# InkTime.net
KiCad netlist of a schematic drawn in EAGLE
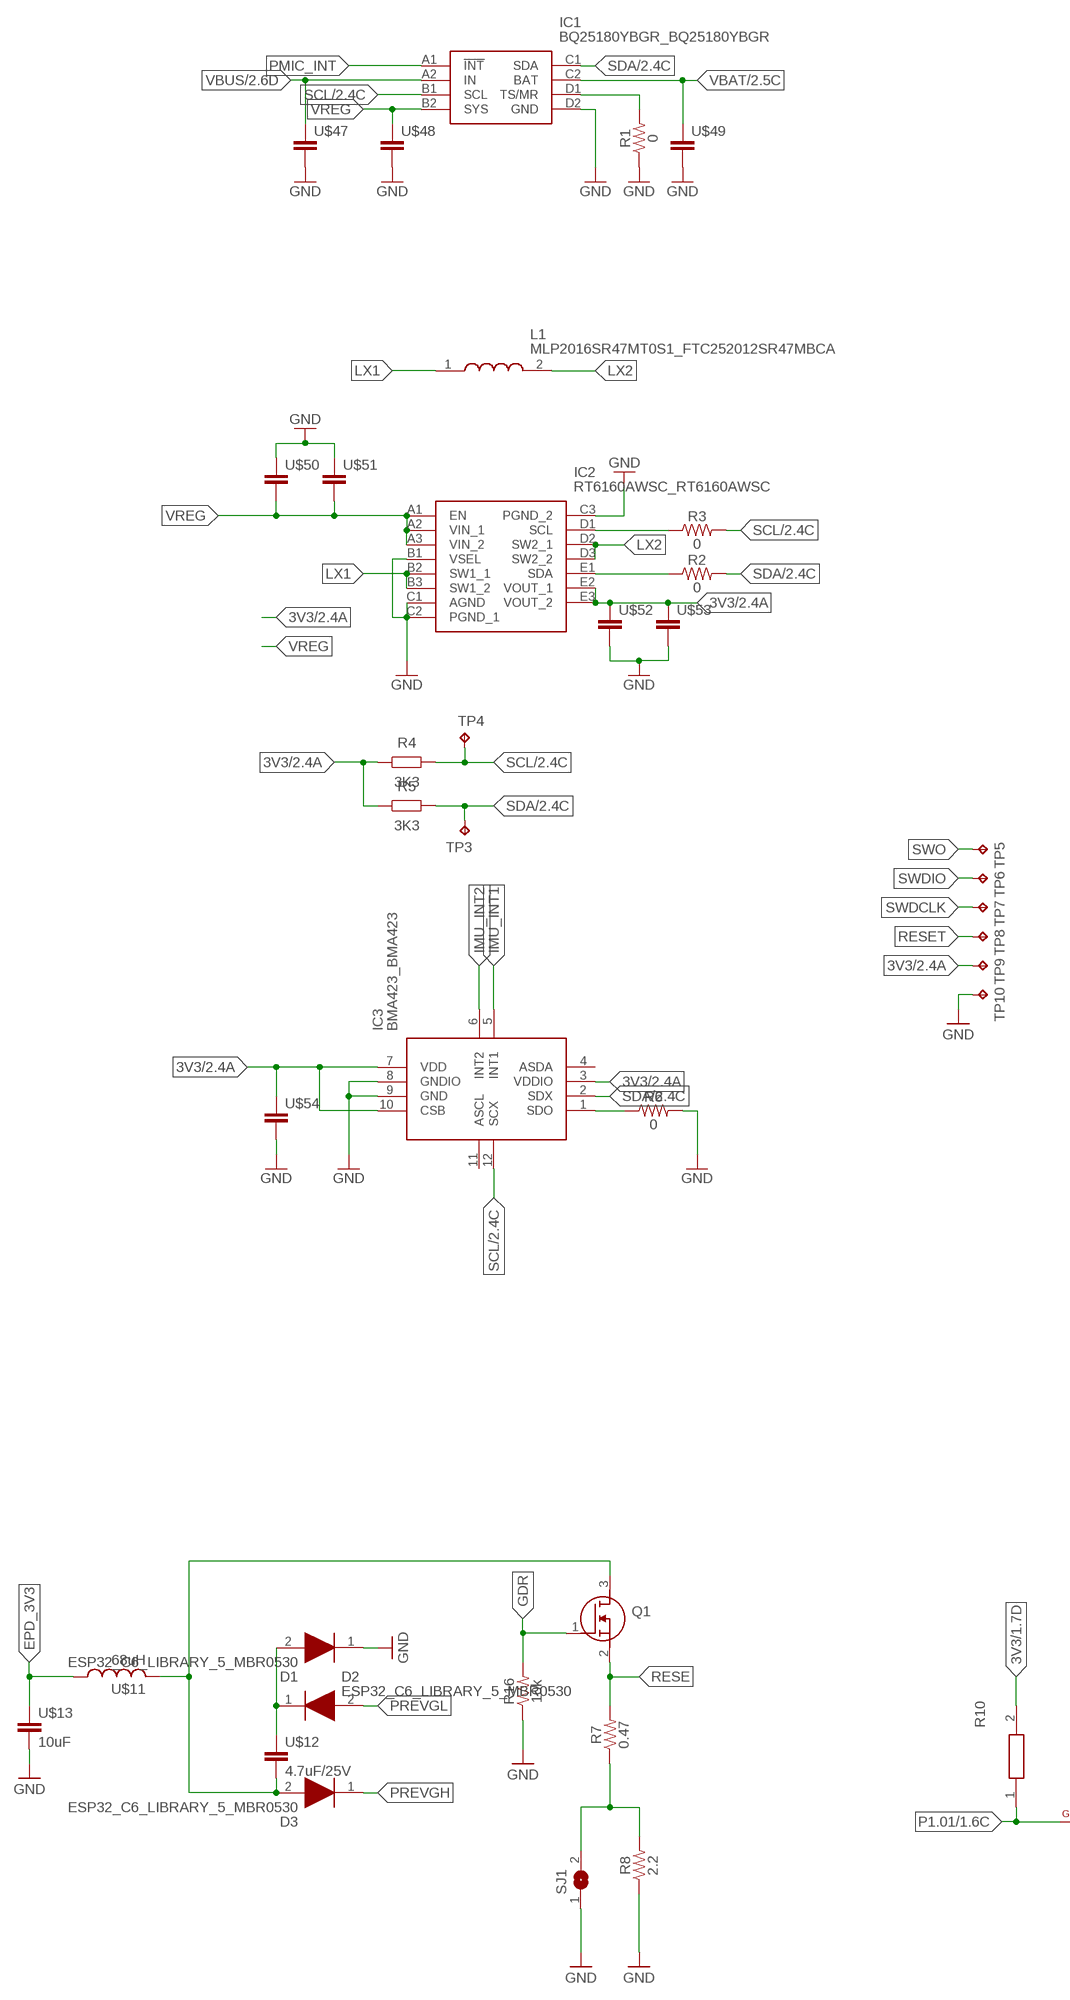
[diagram p0: schematic, sheet 1, part 1 of 3]
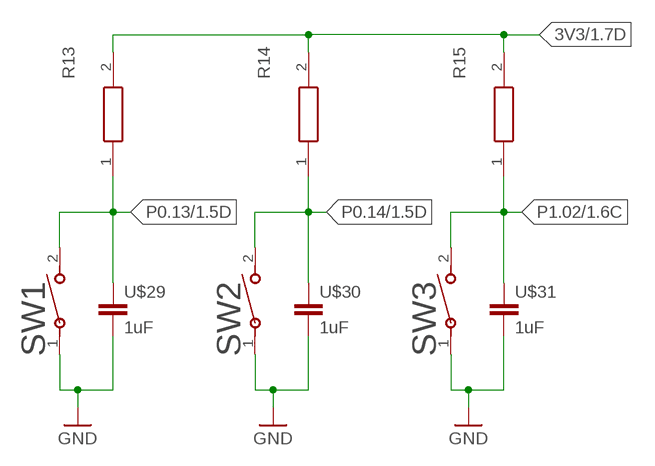
[diagram p1: schematic, sheet 1, part 2 of 3]
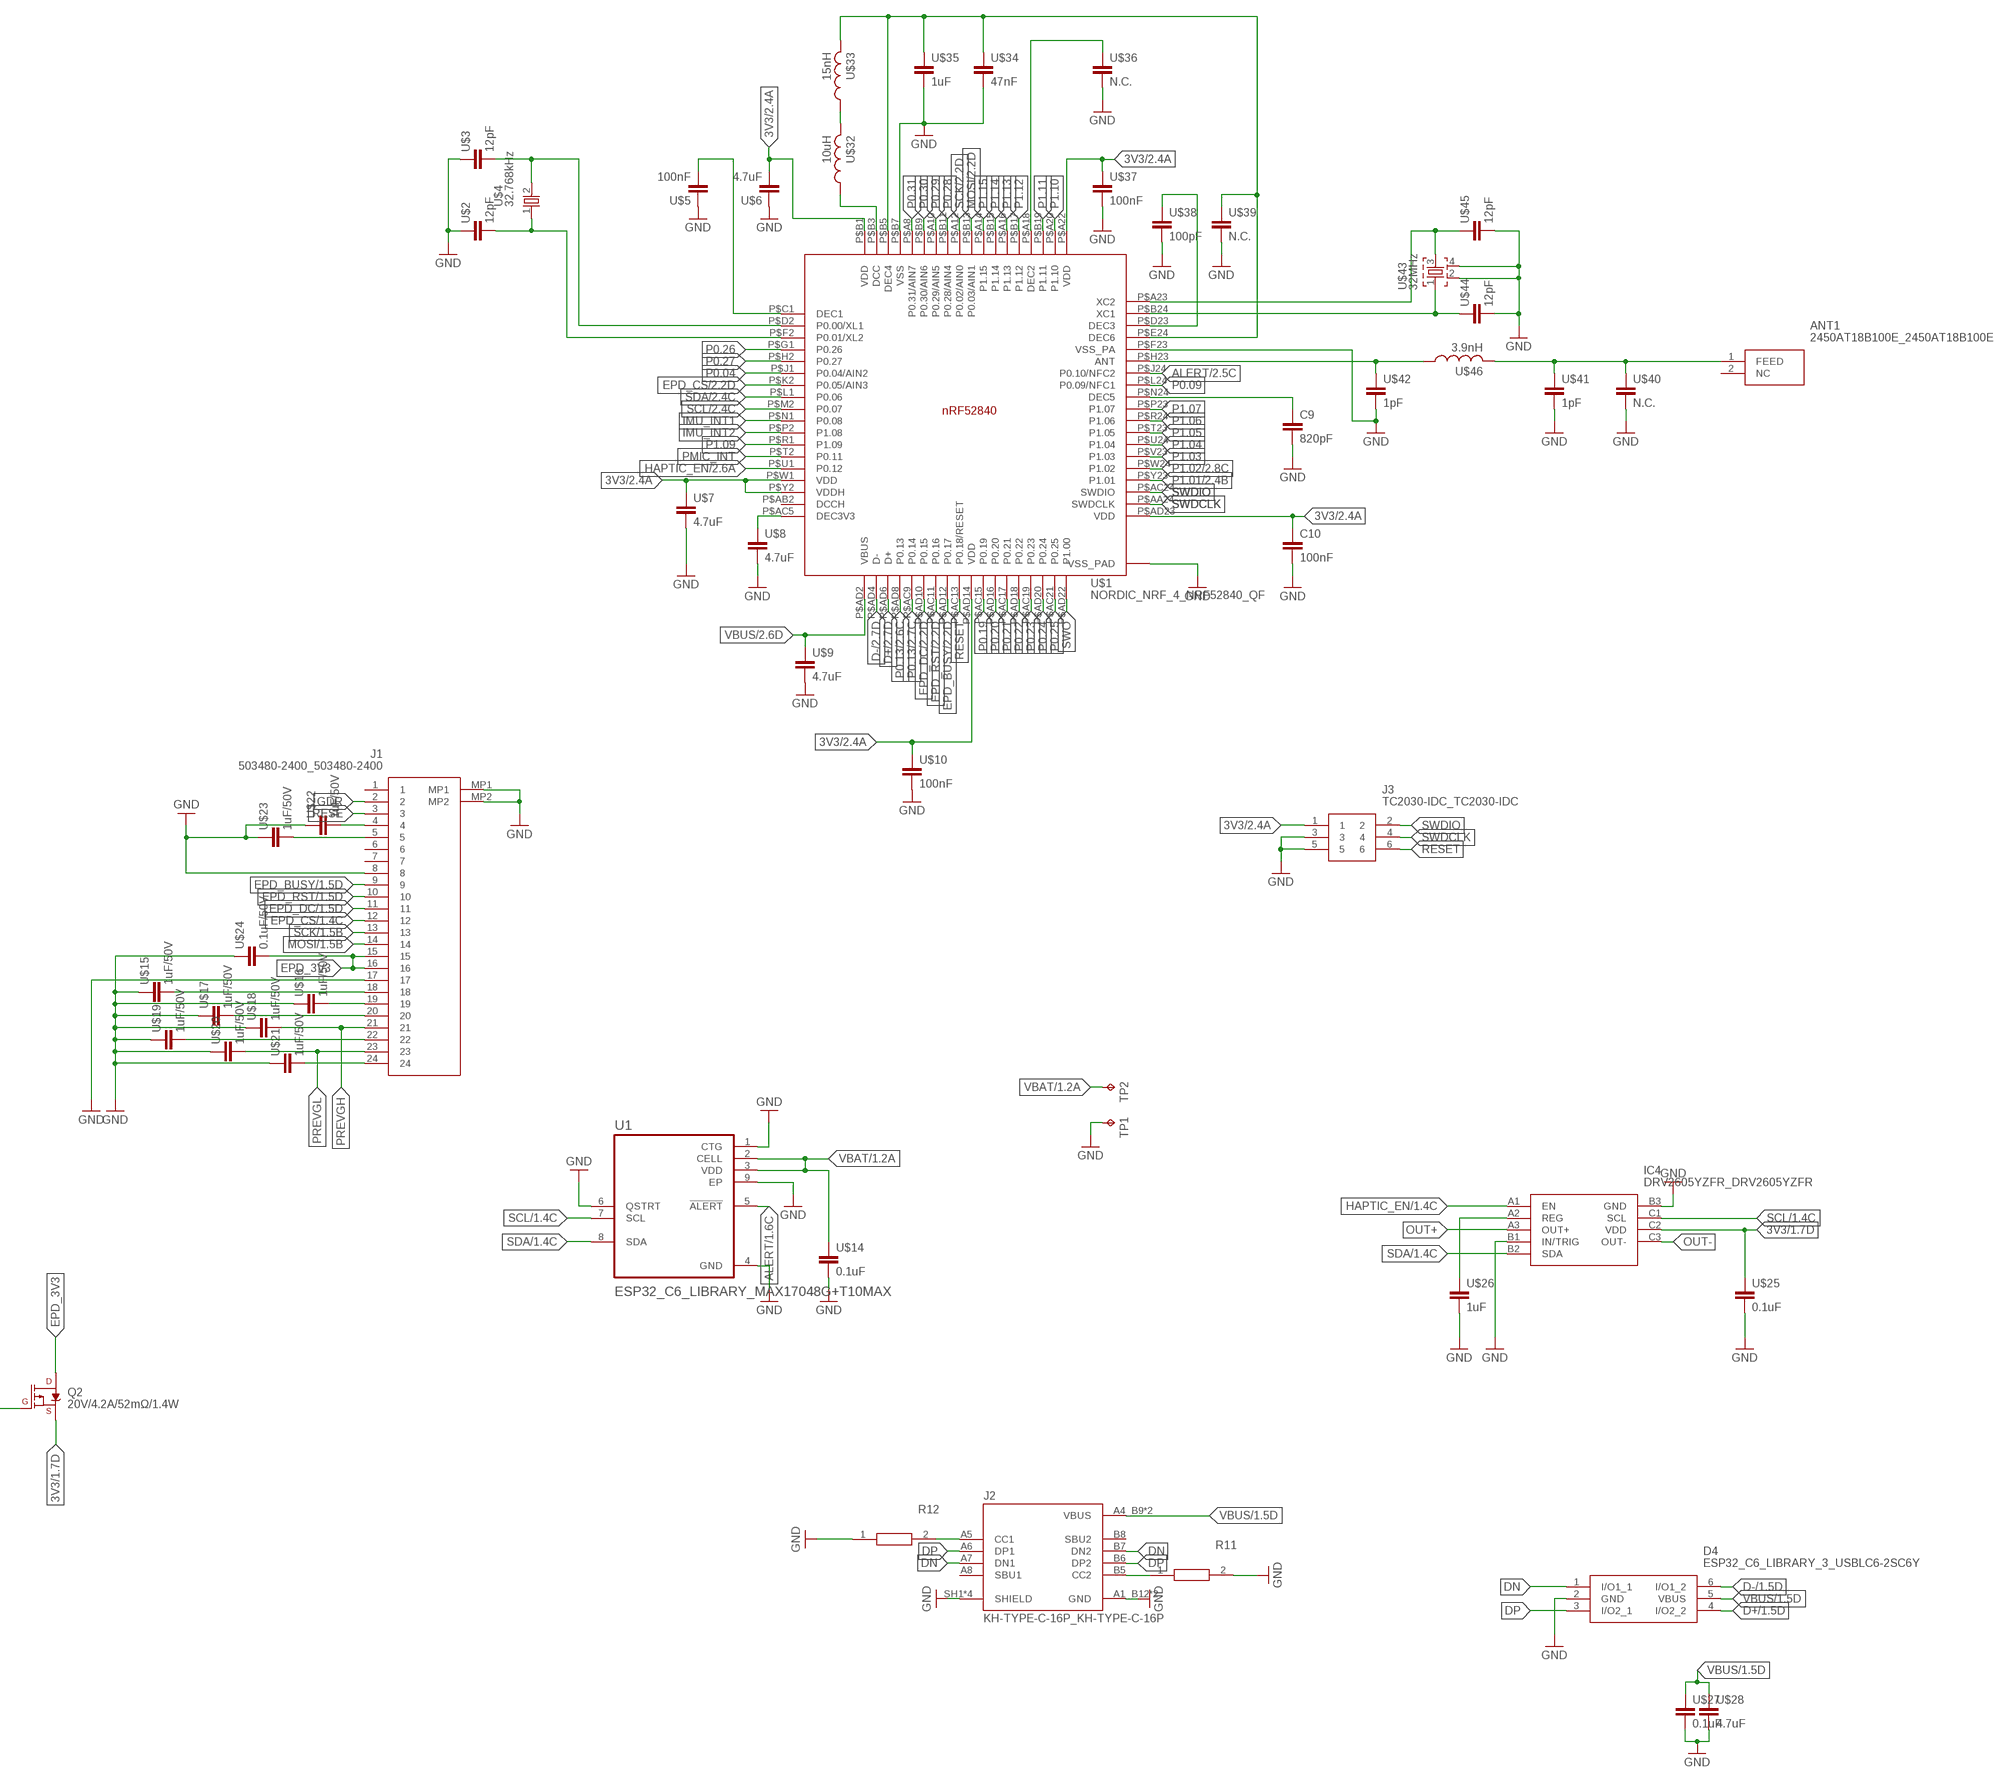
[diagram p2: schematic, sheet 1, part 3 of 3]

(export (version "E")
  (design (tool "Eeschema 10.0.6"))
  (components
    (comp (ref "ANT1")
      (value "2450AT18B100E_2450AT18B100E")
      (footprint "eagle-import:2450AT18B100E_ANTC3216X140N")
      (fields
        (field (name "ARROW_PART_NUMBER") "2450AT18B100E")
        (field (name "MOUSER_PART_NUMBER") "609-2450AT18B100E")
      )
      (libsource (lib "eagle-import") (part "2450AT18B100E_2450AT18B100E"))
    )
    (comp (ref "C9")
      (value "820pF")
      (footprint "eagle-import:PERFECT_0402_0402")
      (libsource (lib "eagle-import") (part "PERFECT_0402_CAP_0402"))
    )
    (comp (ref "C10")
      (value "100nF")
      (footprint "eagle-import:PERFECT_0402_0402")
      (libsource (lib "eagle-import") (part "PERFECT_0402_CAP_0402"))
    )
    (comp (ref "D1")
      (value "ESP32_C6_LIBRARY_5_MBR0530")
      (footprint "eagle-import:ESP32_C6_LIBRARY_5_SOD3716X135N")
      (fields (field (name "MF") "ON Semiconductor") (field (name "MP") "MBR0530"))
      (libsource (lib "eagle-import") (part "ESP32_C6_LIBRARY_5_MBR0530"))
    )
    (comp (ref "D2")
      (value "ESP32_C6_LIBRARY_5_MBR0530")
      (footprint "eagle-import:ESP32_C6_LIBRARY_5_SOD3716X135N")
      (fields (field (name "MF") "ON Semiconductor") (field (name "MP") "MBR0530"))
      (libsource (lib "eagle-import") (part "ESP32_C6_LIBRARY_5_MBR0530"))
    )
    (comp (ref "D3")
      (value "ESP32_C6_LIBRARY_5_MBR0530")
      (footprint "eagle-import:ESP32_C6_LIBRARY_5_SOD3716X135N")
      (fields (field (name "MF") "ON Semiconductor") (field (name "MP") "MBR0530"))
      (libsource (lib "eagle-import") (part "ESP32_C6_LIBRARY_5_MBR0530"))
    )
    (comp (ref "D4")
      (value "ESP32_C6_LIBRARY_3_USBLC6-2SC6Y")
      (footprint "eagle-import:ESP32_C6_LIBRARY_3_SOT95P280X145-6N")
      (fields (field (name "MF") "STMicroelectronics") (field (name "MP") "USBLC6-2SC6Y"))
      (libsource (lib "eagle-import") (part "ESP32_C6_LIBRARY_3_USBLC6-2SC6Y"))
    )
    (comp (ref "IC1")
      (value "BQ25180YBGR_BQ25180YBGR")
      (footprint "eagle-import:BQ25180YBGR_BGA8C40P2X4_100X155X50")
      (fields
        (field (name "ARROW_PART_NUMBER") "BQ25180YBGR")
        (field (name "MOUSER_PART_NUMBER") "595-BQ25180YBGR")
      )
      (libsource (lib "eagle-import") (part "BQ25180YBGR_BQ25180YBGR"))
    )
    (comp (ref "IC2")
      (value "RT6160AWSC_RT6160AWSC")
      (footprint "eagle-import:RT6160AWSC_BGA15C40P3X5_140X230X60")
      (fields
        (field (name "MANUFACTURER_PART_NUMBER") "RT6160AWSC")
        (field (name "MOUSER_PART_NUMBER") "835-RT6160AWSC")
      )
      (libsource (lib "eagle-import") (part "RT6160AWSC_RT6160AWSC"))
    )
    (comp (ref "IC3")
      (value "BMA423_BMA423")
      (footprint "eagle-import:BMA423_BMA423")
      (fields (field (name "ARROW_PART_NUMBER") "BMA423") (field (name "MOUSER_PART_NUMBER") "262-BMA423"))
      (libsource (lib "eagle-import") (part "BMA423_BMA423"))
    )
    (comp (ref "IC4")
      (value "DRV2605YZFR_DRV2605YZFR")
      (footprint "eagle-import:DRV2605YZFR_BGA9C50P3X3_144X144X62")
      (fields (field (name "ARROW_PART_NUMBER") "DRV2605YZFR"))
      (libsource (lib "eagle-import") (part "DRV2605YZFR_DRV2605YZFR"))
    )
    (comp (ref "J1")
      (value "503480-2400_503480-2400")
      (footprint "eagle-import:503480-2400_5034802400")
      (fields
        (field (name "MANUFACTURER_PART_NUMBER") "503480-2400")
        (field (name "MOUSER_PART_NUMBER") "538-503480-2400")
      )
      (libsource (lib "eagle-import") (part "503480-2400_503480-2400"))
    )
    (comp (ref "J2")
      (value "KH-TYPE-C-16P_KH-TYPE-C-16P")
      (footprint "eagle-import:KH-TYPE-C-16P_KINGHELM_KH-TYPE-C-16P")
      (fields (field (name "MF") "kinghelm") (field (name "MP") "KH-TYPE-C-16P"))
      (libsource (lib "eagle-import") (part "KH-TYPE-C-16P_KH-TYPE-C-16P"))
    )
    (comp (ref "J3")
      (value "TC2030-IDC_TC2030-IDC")
      (footprint "eagle-import:TC2030-IDC_TC2030IDC")
      (fields (field (name "MANUFACTURER_PART_NUMBER") "TC2030-IDC"))
      (libsource (lib "eagle-import") (part "TC2030-IDC_TC2030-IDC"))
    )
    (comp (ref "L1")
      (value "MLP2016SR47MT0S1_FTC252012SR47MBCA")
      (footprint "eagle-import:MLP2016SR47MT0S1_INDC2016X100N")
      (fields (field (name "MANUFACTURER_PART_NUMBER") "FTC252012SR47MBCA"))
      (libsource (lib "eagle-import") (part "MLP2016SR47MT0S1_FTC252012SR47MBCA"))
    )
    (comp (ref "Q1")
      (value "ESP32_C6_LIBRARY_6_SI1308EDL-T1-GE3")
      (footprint "eagle-import:ESP32_C6_LIBRARY_6_SOT65P210X110-3N")
      (fields (field (name "MF") "Vishay Siliconix") (field (name "MP") "SI1308EDL-T1-GE3"))
      (libsource (lib "eagle-import") (part "ESP32_C6_LIBRARY_6_SI1308EDL-T1-GE3"))
    )
    (comp (ref "Q2")
      (value "20V/4.2A/52mΩ/1.4W")
      (footprint "eagle-import:ESP32_C6_LIBRARY_4_ESP32_C6_LIBRARY_4_ESP32_C6_LIBRARY_4_ESP32_C6_LIBRARY_4_ESP32_WROVER_SPARKFUN-DISCRETESEMI_SOT23-3")
      (libsource (lib "eagle-import") (part "ESP32_C6_LIBRARY_4_ESP32_WROVER_SPARKFUN-DISCRETESEMI_MOSFET_PCH-DMG2305UX-7"))
    )
    (comp (ref "R1")
      (value "0")
      (footprint "eagle-import:0603")
      (libsource (lib "eagle-import") (part "0OHM-0603-1/10W"))
    )
    (comp (ref "R2")
      (value "0")
      (footprint "eagle-import:0603")
      (libsource (lib "eagle-import") (part "0OHM-0603-1/10W"))
    )
    (comp (ref "R3")
      (value "0")
      (footprint "eagle-import:0603")
      (libsource (lib "eagle-import") (part "0OHM-0603-1/10W"))
    )
    (comp (ref "R4")
      (value "3K3")
      (footprint "eagle-import:RESC1005X40")
      (libsource (lib "eagle-import") (part "RCHIP-0402(1005-METRIC)_"))
    )
    (comp (ref "R5")
      (value "3K3")
      (footprint "eagle-import:RESC1005X40")
      (libsource (lib "eagle-import") (part "RCHIP-0402(1005-METRIC)_"))
    )
    (comp (ref "R6")
      (value "0")
      (footprint "eagle-import:0603")
      (libsource (lib "eagle-import") (part "0OHM-0603-1/10W"))
    )
    (comp (ref "R7")
      (value "0.47")
      (footprint "eagle-import:0603")
      (libsource (lib "eagle-import") (part "0OHM-0603-1/10W"))
    )
    (comp (ref "R8")
      (value "2.2")
      (footprint "eagle-import:0603")
      (libsource (lib "eagle-import") (part "0OHM-0603-1/10W"))
    )
    (comp (ref "R10")
      (value "CPF0201D7K68C1_CPF0201D7K68C1")
      (footprint "eagle-import:CPF0201D7K68C1_0201")
      (libsource (lib "eagle-import") (part "CPF0201D7K68C1_CPF0201D7K68C1"))
    )
    (comp (ref "R11")
      (value "CPF0201D7K68C1_CPF0201D7K68C1")
      (footprint "eagle-import:CPF0201D7K68C1_0201")
      (libsource (lib "eagle-import") (part "CPF0201D7K68C1_CPF0201D7K68C1"))
    )
    (comp (ref "R12")
      (value "5k1")
      (footprint "eagle-import:CPF0201D7K68C1_0201")
      (libsource (lib "eagle-import") (part "CPF0201D7K68C1_CPF0201D7K68C1"))
    )
    (comp (ref "R13")
      (value "CPF0201D7K68C1_CPF0201D7K68C1")
      (footprint "eagle-import:CPF0201D7K68C1_0201")
      (libsource (lib "eagle-import") (part "CPF0201D7K68C1_CPF0201D7K68C1"))
    )
    (comp (ref "R14")
      (value "CPF0201D7K68C1_CPF0201D7K68C1")
      (footprint "eagle-import:CPF0201D7K68C1_0201")
      (libsource (lib "eagle-import") (part "CPF0201D7K68C1_CPF0201D7K68C1"))
    )
    (comp (ref "R15")
      (value "CPF0201D7K68C1_CPF0201D7K68C1")
      (footprint "eagle-import:CPF0201D7K68C1_0201")
      (libsource (lib "eagle-import") (part "CPF0201D7K68C1_CPF0201D7K68C1"))
    )
    (comp (ref "R16")
      (value "10k")
      (footprint "eagle-import:0603")
      (libsource (lib "eagle-import") (part "0OHM-0603-1/10W"))
    )
    (comp (ref "SJ1")
      (value "ESP32_C6_LIBRARY_7_JUMPER_SJ")
      (footprint "eagle-import:ESP32_C6_LIBRARY_7_JUMPER_SJ")
      (libsource (lib "eagle-import") (part "ESP32_C6_LIBRARY_7_JUMPER_SJ"))
    )
    (comp (ref "SW1")
      (value "2025-10-22_07-23-44_LIBRARY_EVP-AKE31AEVP-AKE31A")
      (footprint "eagle-import:2025-10-22_07-23-44_LIBRARY_SW_EVP-AKE31A_PAN")
      (libsource (lib "eagle-import") (part "2025-10-22_07-23-44_LIBRARY_EVP-AKE31AEVP-AKE31A"))
    )
    (comp (ref "SW2")
      (value "2025-10-22_07-23-44_LIBRARY_EVP-AKE31AEVP-AKE31A")
      (footprint "eagle-import:2025-10-22_07-23-44_LIBRARY_SW_EVP-AKE31A_PAN")
      (libsource (lib "eagle-import") (part "2025-10-22_07-23-44_LIBRARY_EVP-AKE31AEVP-AKE31A"))
    )
    (comp (ref "SW3")
      (value "2025-10-22_07-23-44_LIBRARY_EVP-AKE31AEVP-AKE31A")
      (footprint "eagle-import:2025-10-22_07-23-44_LIBRARY_SW_EVP-AKE31A_PAN")
      (libsource (lib "eagle-import") (part "2025-10-22_07-23-44_LIBRARY_EVP-AKE31AEVP-AKE31A"))
    )
    (comp (ref "TP1")
      (value "HECTOR_WATCH_1_TPTP20R")
      (footprint "eagle-import:HECTOR_WATCH_1_TP20R")
      (libsource (lib "eagle-import") (part "HECTOR_WATCH_1_TPTP20R"))
    )
    (comp (ref "TP2")
      (value "HECTOR_WATCH_1_TPTP20R")
      (footprint "eagle-import:HECTOR_WATCH_1_TP20R")
      (libsource (lib "eagle-import") (part "HECTOR_WATCH_1_TPTP20R"))
    )
    (comp (ref "TP3")
      (value "HECTOR_WATCH_1_TPTP20R")
      (footprint "eagle-import:HECTOR_WATCH_1_TP20R")
      (libsource (lib "eagle-import") (part "HECTOR_WATCH_1_TPTP20R"))
    )
    (comp (ref "TP4")
      (value "HECTOR_WATCH_1_TPTP20R")
      (footprint "eagle-import:HECTOR_WATCH_1_TP20R")
      (libsource (lib "eagle-import") (part "HECTOR_WATCH_1_TPTP20R"))
    )
    (comp (ref "TP5")
      (value "HECTOR_WATCH_1_TPTP20R")
      (footprint "eagle-import:HECTOR_WATCH_1_TP20R")
      (libsource (lib "eagle-import") (part "HECTOR_WATCH_1_TPTP20R"))
    )
    (comp (ref "TP6")
      (value "HECTOR_WATCH_1_TPTP20R")
      (footprint "eagle-import:HECTOR_WATCH_1_TP20R")
      (libsource (lib "eagle-import") (part "HECTOR_WATCH_1_TPTP20R"))
    )
    (comp (ref "TP7")
      (value "HECTOR_WATCH_1_TPTP20R")
      (footprint "eagle-import:HECTOR_WATCH_1_TP20R")
      (libsource (lib "eagle-import") (part "HECTOR_WATCH_1_TPTP20R"))
    )
    (comp (ref "TP8")
      (value "HECTOR_WATCH_1_TPTP20R")
      (footprint "eagle-import:HECTOR_WATCH_1_TP20R")
      (libsource (lib "eagle-import") (part "HECTOR_WATCH_1_TPTP20R"))
    )
    (comp (ref "TP9")
      (value "HECTOR_WATCH_1_TPTP20R")
      (footprint "eagle-import:HECTOR_WATCH_1_TP20R")
      (libsource (lib "eagle-import") (part "HECTOR_WATCH_1_TPTP20R"))
    )
    (comp (ref "TP10")
      (value "HECTOR_WATCH_1_TPTP20R")
      (footprint "eagle-import:HECTOR_WATCH_1_TP20R")
      (libsource (lib "eagle-import") (part "HECTOR_WATCH_1_TPTP20R"))
    )
    (comp (ref "U$1")
      (value "NORDIC_NRF_4_NRF52840_QF")
      (footprint "eagle-import:NORDIC_NRF_4_AQFN50P700X700X85_HS-74N")
      (libsource (lib "eagle-import") (part "NORDIC_NRF_4_NRF52840_QF"))
    )
    (comp (ref "U$2")
      (value "12pF")
      (footprint "eagle-import:NORDIC_NRF_3_RESC0201_L")
      (libsource (lib "eagle-import") (part "NORDIC_NRF_3_CAPACITOR_0201_L"))
    )
    (comp (ref "U$3")
      (value "12pF")
      (footprint "eagle-import:NORDIC_NRF_3_RESC0201_L")
      (libsource (lib "eagle-import") (part "NORDIC_NRF_3_CAPACITOR_0201_L"))
    )
    (comp (ref "U$4")
      (value "32.768kHz")
      (footprint "eagle-import:NORDIC_NRF_1_XTAL_3215_N")
      (libsource (lib "eagle-import") (part "NORDIC_NRF_1_XTAL_32KHZ"))
    )
    (comp (ref "U$5")
      (value "100nF")
      (footprint "eagle-import:NORDIC_NRF_3_RESC0201_L")
      (libsource (lib "eagle-import") (part "NORDIC_NRF_3_CAPACITOR_0201_L"))
    )
    (comp (ref "U$6")
      (value "4.7uF")
      (footprint "eagle-import:NORDIC_NRF_3_RESC0201_L")
      (libsource (lib "eagle-import") (part "NORDIC_NRF_3_CAPACITOR_0201_L"))
    )
    (comp (ref "U$7")
      (value "4.7uF")
      (footprint "eagle-import:NORDIC_NRF_3_RESC0201_L")
      (libsource (lib "eagle-import") (part "NORDIC_NRF_3_CAPACITOR_0201_L"))
    )
    (comp (ref "U$8")
      (value "4.7uF")
      (footprint "eagle-import:NORDIC_NRF_3_RESC0201_L")
      (libsource (lib "eagle-import") (part "NORDIC_NRF_3_CAPACITOR_0201_L"))
    )
    (comp (ref "U$9")
      (value "4.7uF")
      (footprint "eagle-import:NORDIC_NRF_3_RESC0201_L")
      (libsource (lib "eagle-import") (part "NORDIC_NRF_3_CAPACITOR_0201_L"))
    )
    (comp (ref "U$10")
      (value "100nF")
      (footprint "eagle-import:NORDIC_NRF_3_RESC0201_L")
      (libsource (lib "eagle-import") (part "NORDIC_NRF_3_CAPACITOR_0201_L"))
    )
    (comp (ref "U$11")
      (value "68uH")
      (footprint "eagle-import:NORDIC_NRF_2_RESC0402_L")
      (libsource (lib "eagle-import") (part "NORDIC_NRF_2_INDUCTOR_0402_L"))
    )
    (comp (ref "U$12")
      (value "4.7uF/25V")
      (footprint "eagle-import:NORDIC_NRF_3_RESC0201_L")
      (libsource (lib "eagle-import") (part "NORDIC_NRF_3_CAPACITOR_0201_L"))
    )
    (comp (ref "U$13")
      (value "10uF")
      (footprint "eagle-import:NORDIC_NRF_3_RESC0201_L")
      (libsource (lib "eagle-import") (part "NORDIC_NRF_3_CAPACITOR_0201_L"))
    )
    (comp (ref "U$14")
      (value "0.1uF")
      (footprint "eagle-import:NORDIC_NRF_3_RESC0201_L")
      (libsource (lib "eagle-import") (part "NORDIC_NRF_3_CAPACITOR_0201_L"))
    )
    (comp (ref "U$15")
      (value "1uF/50V")
      (footprint "eagle-import:NORDIC_NRF_3_RESC0201_L")
      (libsource (lib "eagle-import") (part "NORDIC_NRF_3_CAPACITOR_0201_L"))
    )
    (comp (ref "U$16")
      (value "1uF/50V")
      (footprint "eagle-import:NORDIC_NRF_3_RESC0201_L")
      (libsource (lib "eagle-import") (part "NORDIC_NRF_3_CAPACITOR_0201_L"))
    )
    (comp (ref "U$17")
      (value "1uF/50V")
      (footprint "eagle-import:NORDIC_NRF_3_RESC0201_L")
      (libsource (lib "eagle-import") (part "NORDIC_NRF_3_CAPACITOR_0201_L"))
    )
    (comp (ref "U$18")
      (value "1uF/50V")
      (footprint "eagle-import:NORDIC_NRF_3_RESC0201_L")
      (libsource (lib "eagle-import") (part "NORDIC_NRF_3_CAPACITOR_0201_L"))
    )
    (comp (ref "U$19")
      (value "1uF/50V")
      (footprint "eagle-import:NORDIC_NRF_3_RESC0201_L")
      (libsource (lib "eagle-import") (part "NORDIC_NRF_3_CAPACITOR_0201_L"))
    )
    (comp (ref "U$20")
      (value "1uF/50V")
      (footprint "eagle-import:NORDIC_NRF_3_RESC0201_L")
      (libsource (lib "eagle-import") (part "NORDIC_NRF_3_CAPACITOR_0201_L"))
    )
    (comp (ref "U$21")
      (value "1uF/50V")
      (footprint "eagle-import:NORDIC_NRF_3_RESC0201_L")
      (libsource (lib "eagle-import") (part "NORDIC_NRF_3_CAPACITOR_0201_L"))
    )
    (comp (ref "U$22")
      (value "1uF/50V")
      (footprint "eagle-import:NORDIC_NRF_3_RESC0201_L")
      (libsource (lib "eagle-import") (part "NORDIC_NRF_3_CAPACITOR_0201_L"))
    )
    (comp (ref "U$23")
      (value "1uF/50V")
      (footprint "eagle-import:NORDIC_NRF_3_RESC0201_L")
      (libsource (lib "eagle-import") (part "NORDIC_NRF_3_CAPACITOR_0201_L"))
    )
    (comp (ref "U$24")
      (value "0.1uF/50V")
      (footprint "eagle-import:NORDIC_NRF_3_RESC0201_L")
      (libsource (lib "eagle-import") (part "NORDIC_NRF_3_CAPACITOR_0201_L"))
    )
    (comp (ref "U$25")
      (value "0.1uF")
      (footprint "eagle-import:NORDIC_NRF_3_RESC0201_L")
      (libsource (lib "eagle-import") (part "NORDIC_NRF_3_CAPACITOR_0201_L"))
    )
    (comp (ref "U$26")
      (value "1uF")
      (footprint "eagle-import:NORDIC_NRF_3_RESC0201_L")
      (libsource (lib "eagle-import") (part "NORDIC_NRF_3_CAPACITOR_0201_L"))
    )
    (comp (ref "U$27")
      (value "0.1uF")
      (footprint "eagle-import:NORDIC_NRF_3_RESC0201_L")
      (libsource (lib "eagle-import") (part "NORDIC_NRF_3_CAPACITOR_0201_L"))
    )
    (comp (ref "U$28")
      (value "4.7uF")
      (footprint "eagle-import:NORDIC_NRF_3_RESC0201_L")
      (libsource (lib "eagle-import") (part "NORDIC_NRF_3_CAPACITOR_0201_L"))
    )
    (comp (ref "U$29")
      (value "1uF")
      (footprint "eagle-import:NORDIC_NRF_3_RESC0201_L")
      (libsource (lib "eagle-import") (part "NORDIC_NRF_3_CAPACITOR_0201_L"))
    )
    (comp (ref "U$30")
      (value "1uF")
      (footprint "eagle-import:NORDIC_NRF_3_RESC0201_L")
      (libsource (lib "eagle-import") (part "NORDIC_NRF_3_CAPACITOR_0201_L"))
    )
    (comp (ref "U$31")
      (value "1uF")
      (footprint "eagle-import:NORDIC_NRF_3_RESC0201_L")
      (libsource (lib "eagle-import") (part "NORDIC_NRF_3_CAPACITOR_0201_L"))
    )
    (comp (ref "U$32")
      (value "10uH")
      (footprint "eagle-import:NORDIC_NRF_2_RESC0402_L")
      (libsource (lib "eagle-import") (part "NORDIC_NRF_2_INDUCTOR_0402_L"))
    )
    (comp (ref "U$33")
      (value "15nH")
      (footprint "eagle-import:NORDIC_NRF_2_RESC0402_L")
      (libsource (lib "eagle-import") (part "NORDIC_NRF_2_INDUCTOR_0402_L"))
    )
    (comp (ref "U$34")
      (value "47nF")
      (footprint "eagle-import:NORDIC_NRF_3_RESC0201_L")
      (libsource (lib "eagle-import") (part "NORDIC_NRF_3_CAPACITOR_0201_L"))
    )
    (comp (ref "U$35")
      (value "1uF")
      (footprint "eagle-import:NORDIC_NRF_3_RESC0201_L")
      (libsource (lib "eagle-import") (part "NORDIC_NRF_3_CAPACITOR_0201_L"))
    )
    (comp (ref "U$36")
      (value "N.C.")
      (footprint "eagle-import:NORDIC_NRF_3_RESC0201_L")
      (libsource (lib "eagle-import") (part "NORDIC_NRF_3_CAPACITOR_0201_L"))
    )
    (comp (ref "U$37")
      (value "100nF")
      (footprint "eagle-import:NORDIC_NRF_3_RESC0201_L")
      (libsource (lib "eagle-import") (part "NORDIC_NRF_3_CAPACITOR_0201_L"))
    )
    (comp (ref "U$38")
      (value "100pF")
      (footprint "eagle-import:NORDIC_NRF_3_RESC0201_L")
      (libsource (lib "eagle-import") (part "NORDIC_NRF_3_CAPACITOR_0201_L"))
    )
    (comp (ref "U$39")
      (value "N.C.")
      (footprint "eagle-import:NORDIC_NRF_3_RESC0201_L")
      (libsource (lib "eagle-import") (part "NORDIC_NRF_3_CAPACITOR_0201_L"))
    )
    (comp (ref "U$40")
      (value "N.C.")
      (footprint "eagle-import:NORDIC_NRF_3_RESC0201_L")
      (libsource (lib "eagle-import") (part "NORDIC_NRF_3_CAPACITOR_0201_L"))
    )
    (comp (ref "U$41")
      (value "1pF")
      (footprint "eagle-import:NORDIC_NRF_3_RESC0201_L")
      (libsource (lib "eagle-import") (part "NORDIC_NRF_3_CAPACITOR_0201_L"))
    )
    (comp (ref "U$42")
      (value "1pF")
      (footprint "eagle-import:NORDIC_NRF_3_RESC0201_L")
      (libsource (lib "eagle-import") (part "NORDIC_NRF_3_CAPACITOR_0201_L"))
    )
    (comp (ref "U$43")
      (value "32MHz")
      (footprint "eagle-import:NORDIC_NRF_BT-XTAL_2016_N")
      (libsource (lib "eagle-import") (part "NORDIC_NRF_XTAL_32MHZ"))
    )
    (comp (ref "U$44")
      (value "12pF")
      (footprint "eagle-import:NORDIC_NRF_3_RESC0201_L")
      (libsource (lib "eagle-import") (part "NORDIC_NRF_3_CAPACITOR_0201_L"))
    )
    (comp (ref "U$45")
      (value "12pF")
      (footprint "eagle-import:NORDIC_NRF_3_RESC0201_L")
      (libsource (lib "eagle-import") (part "NORDIC_NRF_3_CAPACITOR_0201_L"))
    )
    (comp (ref "U$46")
      (value "3.9nH")
      (footprint "eagle-import:NORDIC_NRF_2_RESC0402_L")
      (libsource (lib "eagle-import") (part "NORDIC_NRF_2_INDUCTOR_0402_L"))
    )
    (comp (ref "U$47")
      (value "NORDIC_NRF_3_CAPACITOR_0201_L")
      (footprint "eagle-import:NORDIC_NRF_3_RESC0201_L")
      (libsource (lib "eagle-import") (part "NORDIC_NRF_3_CAPACITOR_0201_L"))
    )
    (comp (ref "U$48")
      (value "NORDIC_NRF_3_CAPACITOR_0201_L")
      (footprint "eagle-import:NORDIC_NRF_3_RESC0201_L")
      (libsource (lib "eagle-import") (part "NORDIC_NRF_3_CAPACITOR_0201_L"))
    )
    (comp (ref "U$49")
      (value "NORDIC_NRF_3_CAPACITOR_0201_L")
      (footprint "eagle-import:NORDIC_NRF_3_RESC0201_L")
      (libsource (lib "eagle-import") (part "NORDIC_NRF_3_CAPACITOR_0201_L"))
    )
    (comp (ref "U$50")
      (value "NORDIC_NRF_3_CAPACITOR_0201_L")
      (footprint "eagle-import:NORDIC_NRF_3_RESC0201_L")
      (libsource (lib "eagle-import") (part "NORDIC_NRF_3_CAPACITOR_0201_L"))
    )
    (comp (ref "U$51")
      (value "NORDIC_NRF_3_CAPACITOR_0201_L")
      (footprint "eagle-import:NORDIC_NRF_3_RESC0201_L")
      (libsource (lib "eagle-import") (part "NORDIC_NRF_3_CAPACITOR_0201_L"))
    )
    (comp (ref "U$52")
      (value "NORDIC_NRF_3_CAPACITOR_0201_L")
      (footprint "eagle-import:NORDIC_NRF_3_RESC0201_L")
      (libsource (lib "eagle-import") (part "NORDIC_NRF_3_CAPACITOR_0201_L"))
    )
    (comp (ref "U$53")
      (value "NORDIC_NRF_3_CAPACITOR_0201_L")
      (footprint "eagle-import:NORDIC_NRF_3_RESC0201_L")
      (libsource (lib "eagle-import") (part "NORDIC_NRF_3_CAPACITOR_0201_L"))
    )
    (comp (ref "U$54")
      (value "NORDIC_NRF_3_CAPACITOR_0201_L")
      (footprint "eagle-import:NORDIC_NRF_3_RESC0201_L")
      (libsource (lib "eagle-import") (part "NORDIC_NRF_3_CAPACITOR_0201_L"))
    )
    (comp (ref "U1")
      (value "ESP32_C6_LIBRARY_MAX17048G+T10MAX")
      (footprint "eagle-import:ESP32_C6_LIBRARY_SON50P200X200X80-9N")
      (libsource (lib "eagle-import") (part "ESP32_C6_LIBRARY_MAX17048G+T10MAX"))
    )
  )
  (nets
    (net (code "1") (name "3V3{slash}1.7D") (class "Default")
      (node (ref "IC4") (pin "C2") (pinfunction "VDD_C2") (pintype "bidirectional"))
      (node (ref "Q2") (pin "2") (pinfunction "S_2") (pintype "bidirectional"))
      (node (ref "R10") (pin "2") (pinfunction "2_2") (pintype "bidirectional"))
      (node (ref "R13") (pin "2") (pinfunction "2_2") (pintype "bidirectional"))
      (node (ref "R14") (pin "2") (pinfunction "2_2") (pintype "bidirectional"))
      (node (ref "R15") (pin "2") (pinfunction "2_2") (pintype "bidirectional"))
      (node (ref "U$25") (pin "1") (pinfunction "1_1") (pintype "passive"))
    )
    (net (code "2") (name "3V3{slash}2.4A") (class "Default")
      (node (ref "C10") (pin "1") (pinfunction "1_1") (pintype "passive"))
      (node (ref "IC2") (pin "E2") (pinfunction "VOUT_1_E2") (pintype "bidirectional"))
      (node (ref "IC2") (pin "E3") (pinfunction "VOUT_2_E3") (pintype "bidirectional"))
      (node (ref "IC3") (pin "10") (pinfunction "CSB_10") (pintype "bidirectional"))
      (node (ref "IC3") (pin "3") (pinfunction "VDDIO_3") (pintype "bidirectional"))
      (node (ref "IC3") (pin "7") (pinfunction "VDD_7") (pintype "bidirectional"))
      (node (ref "J3") (pin "1") (pinfunction "1_1") (pintype "bidirectional"))
      (node (ref "R4") (pin "1") (pinfunction "1_1") (pintype "passive"))
      (node (ref "R5") (pin "1") (pinfunction "1_1") (pintype "passive"))
      (node (ref "TP9") (pin "TP") (pinfunction "TP_TP") (pintype "input"))
      (node (ref "U$1") (pin "P$A22") (pinfunction "VDD_P$A22") (pintype "power_in"))
      (node (ref "U$1") (pin "P$AD14") (pinfunction "VDD_P$AD14") (pintype "power_in"))
      (node (ref "U$1") (pin "P$AD23") (pinfunction "VDD_P$AD23") (pintype "power_in"))
      (node (ref "U$1") (pin "P$B1") (pinfunction "VDD_P$B1") (pintype "power_in"))
      (node (ref "U$1") (pin "P$W1") (pinfunction "VDD_P$W1") (pintype "power_in"))
      (node (ref "U$1") (pin "P$Y2") (pinfunction "VDDH_P$Y2") (pintype "power_in"))
      (node (ref "U$10") (pin "1") (pinfunction "1_1") (pintype "passive"))
      (node (ref "U$37") (pin "1") (pinfunction "1_1") (pintype "passive"))
      (node (ref "U$52") (pin "1") (pinfunction "1_1") (pintype "passive"))
      (node (ref "U$53") (pin "1") (pinfunction "1_1") (pintype "passive"))
      (node (ref "U$54") (pin "1") (pinfunction "1_1") (pintype "passive"))
      (node (ref "U$6") (pin "2") (pinfunction "2_2") (pintype "passive"))
      (node (ref "U$7") (pin "1") (pinfunction "1_1") (pintype "passive"))
    )
    (net (code "3") (name "ALERT{slash}1.6C") (class "Default")
      (node (ref "U1") (pin "5") (pinfunction "~{ALERT}_5") (pintype "output"))
    )
    (net (code "4") (name "ALERT{slash}2.5C") (class "Default")
      (node (ref "U$1") (pin "P$J24") (pinfunction "P0.10/NFC2_P$J24") (pintype "bidirectional"))
    )
    (net (code "5") (name "D+{slash}1.5D") (class "Default")
      (node (ref "D4") (pin "4") (pinfunction "I/O2_2_4") (pintype "bidirectional"))
    )
    (net (code "6") (name "D+{slash}2.7D") (class "Default")
      (node (ref "U$1") (pin "P$AD6") (pinfunction "D+_P$AD6") (pintype "bidirectional"))
    )
    (net (code "7") (name "D-{slash}1.5D") (class "Default")
      (node (ref "D4") (pin "6") (pinfunction "I/O1_2_6") (pintype "bidirectional"))
    )
    (net (code "8") (name "D-{slash}2.7D") (class "Default")
      (node (ref "U$1") (pin "P$AD4") (pinfunction "D-_P$AD4") (pintype "bidirectional"))
    )
    (net (code "9") (name "DN") (class "Default")
      (node (ref "D4") (pin "1") (pinfunction "I/O1_1_1") (pintype "bidirectional"))
      (node (ref "J2") (pin "A7") (pinfunction "DN1_A7") (pintype "bidirectional"))
      (node (ref "J2") (pin "B7") (pinfunction "DN2_B7") (pintype "bidirectional"))
    )
    (net (code "10") (name "DP") (class "Default")
      (node (ref "D4") (pin "3") (pinfunction "I/O2_1_3") (pintype "bidirectional"))
      (node (ref "J2") (pin "A6") (pinfunction "DP1_A6") (pintype "bidirectional"))
      (node (ref "J2") (pin "B6") (pinfunction "DP2_B6") (pintype "bidirectional"))
    )
    (net (code "11") (name "EPD_3V3") (class "Default")
      (node (ref "J1") (pin "15") (pinfunction "15_15") (pintype "bidirectional"))
      (node (ref "J1") (pin "16") (pinfunction "16_16") (pintype "bidirectional"))
      (node (ref "Q2") (pin "3") (pinfunction "D_3") (pintype "bidirectional"))
      (node (ref "U$11") (pin "1") (pinfunction "1_1") (pintype "passive"))
      (node (ref "U$13") (pin "1") (pinfunction "1_1") (pintype "passive"))
      (node (ref "U$24") (pin "2") (pinfunction "2_2") (pintype "passive"))
    )
    (net (code "12") (name "EPD_BUSY{slash}1.5D") (class "Default")
      (node (ref "J1") (pin "9") (pinfunction "9_9") (pintype "bidirectional"))
    )
    (net (code "13") (name "EPD_BUSY{slash}2.2D") (class "Default")
      (node (ref "U$1") (pin "P$AD12") (pinfunction "P0.17_P$AD12") (pintype "bidirectional"))
    )
    (net (code "14") (name "EPD_CS{slash}1.4C") (class "Default")
      (node (ref "J1") (pin "12") (pinfunction "12_12") (pintype "bidirectional"))
    )
    (net (code "15") (name "EPD_CS{slash}2.2D") (class "Default")
      (node (ref "U$1") (pin "P$K2") (pinfunction "P0.05/AIN3_P$K2") (pintype "bidirectional"))
    )
    (net (code "16") (name "EPD_DC{slash}1.5D") (class "Default")
      (node (ref "J1") (pin "11") (pinfunction "11_11") (pintype "bidirectional"))
    )
    (net (code "17") (name "EPD_DC{slash}2.2D") (class "Default")
      (node (ref "U$1") (pin "P$AD10") (pinfunction "P0.15_P$AD10") (pintype "bidirectional"))
    )
    (net (code "18") (name "EPD_RST{slash}1.5D") (class "Default")
      (node (ref "J1") (pin "10") (pinfunction "10_10") (pintype "bidirectional"))
    )
    (net (code "19") (name "EPD_RST{slash}2.2D") (class "Default")
      (node (ref "U$1") (pin "P$AC11") (pinfunction "P0.16_P$AC11") (pintype "bidirectional"))
    )
    (net (code "20") (name "GDR") (class "Default")
      (node (ref "J1") (pin "2") (pinfunction "2_2") (pintype "bidirectional"))
      (node (ref "Q1") (pin "1") (pinfunction "G_1") (pintype "bidirectional"))
      (node (ref "R16") (pin "2") (pinfunction "2_2") (pintype "passive"))
    )
    (net (code "21") (name "GND") (class "Default")
      (node (ref "C10") (pin "2") (pinfunction "2_2") (pintype "passive"))
      (node (ref "C9") (pin "2") (pinfunction "2_2") (pintype "passive"))
      (node (ref "D1") (pin "1") (pinfunction "K_1") (pintype "bidirectional"))
      (node (ref "D4") (pin "2") (pinfunction "GND_2") (pintype "bidirectional"))
      (node (ref "IC1") (pin "D2") (pinfunction "GND_D2") (pintype "bidirectional"))
      (node (ref "IC2") (pin "B1") (pinfunction "VSEL_B1") (pintype "bidirectional"))
      (node (ref "IC2") (pin "C1") (pinfunction "AGND_C1") (pintype "bidirectional"))
      (node (ref "IC2") (pin "C2") (pinfunction "PGND_1_C2") (pintype "bidirectional"))
      (node (ref "IC2") (pin "C3") (pinfunction "PGND_2_C3") (pintype "bidirectional"))
      (node (ref "IC3") (pin "8") (pinfunction "GNDIO_8") (pintype "bidirectional"))
      (node (ref "IC3") (pin "9") (pinfunction "GND_9") (pintype "bidirectional"))
      (node (ref "IC4") (pin "B1") (pinfunction "IN/TRIG_B1") (pintype "bidirectional"))
      (node (ref "IC4") (pin "B3") (pinfunction "GND_B3") (pintype "bidirectional"))
      (node (ref "J1") (pin "17") (pinfunction "17_17") (pintype "bidirectional"))
      (node (ref "J1") (pin "8") (pinfunction "8_8") (pintype "bidirectional"))
      (node (ref "J1") (pin "MP1") (pinfunction "MP1_MP1") (pintype "bidirectional"))
      (node (ref "J1") (pin "MP2") (pinfunction "MP2_MP2") (pintype "bidirectional"))
      (node (ref "J2") (pin "A12_B1") (pinfunction "GND_A12_B1") (pintype "power_in"))
      (node (ref "J2") (pin "A1_B12") (pinfunction "GND_A1_B12") (pintype "power_in"))
      (node (ref "J2") (pin "SH1") (pinfunction "SHIELD_SH1") (pintype "passive"))
      (node (ref "J2") (pin "SH2") (pinfunction "SHIELD_SH2") (pintype "passive"))
      (node (ref "J2") (pin "SH3") (pinfunction "SHIELD_SH3") (pintype "passive"))
      (node (ref "J2") (pin "SH4") (pinfunction "SHIELD_SH4") (pintype "passive"))
      (node (ref "J3") (pin "3") (pinfunction "3_3") (pintype "bidirectional"))
      (node (ref "J3") (pin "5") (pinfunction "5_5") (pintype "bidirectional"))
      (node (ref "R1") (pin "1") (pinfunction "1_1") (pintype "passive"))
      (node (ref "R11") (pin "2") (pinfunction "2_2") (pintype "bidirectional"))
      (node (ref "R12") (pin "1") (pinfunction "1_1") (pintype "bidirectional"))
      (node (ref "R16") (pin "1") (pinfunction "1_1") (pintype "passive"))
      (node (ref "R6") (pin "2") (pinfunction "2_2") (pintype "passive"))
      (node (ref "R8") (pin "1") (pinfunction "1_1") (pintype "passive"))
      (node (ref "SJ1") (pin "1") (pinfunction "1_1") (pintype "passive"))
      (node (ref "SW1") (pin "1") (pinfunction "1_1") (pintype "passive"))
      (node (ref "SW2") (pin "1") (pinfunction "1_1") (pintype "passive"))
      (node (ref "SW3") (pin "1") (pinfunction "1_1") (pintype "passive"))
      (node (ref "TP1") (pin "TP") (pinfunction "TP_TP") (pintype "input"))
      (node (ref "TP10") (pin "TP") (pinfunction "TP_TP") (pintype "input"))
      (node (ref "U$1") (pin "P$74") (pinfunction "VSS_PAD_P$74") (pintype "bidirectional"))
      (node (ref "U$1") (pin "P$75") (pinfunction "VSS_PAD_P$75") (pintype "bidirectional"))
      (node (ref "U$1") (pin "P$76") (pinfunction "VSS_PAD_P$76") (pintype "bidirectional"))
      (node (ref "U$1") (pin "P$77") (pinfunction "VSS_PAD_P$77") (pintype "bidirectional"))
      (node (ref "U$1") (pin "P$78") (pinfunction "VSS_PAD_P$78") (pintype "bidirectional"))
      (node (ref "U$1") (pin "P$79") (pinfunction "VSS_PAD_P$79") (pintype "bidirectional"))
      (node (ref "U$1") (pin "P$80") (pinfunction "VSS_PAD_P$80") (pintype "bidirectional"))
      (node (ref "U$1") (pin "P$81") (pinfunction "VSS_PAD_P$81") (pintype "bidirectional"))
      (node (ref "U$1") (pin "P$82") (pinfunction "VSS_PAD_P$82") (pintype "bidirectional"))
      (node (ref "U$1") (pin "P$83") (pinfunction "VSS_PAD_P$83") (pintype "bidirectional"))
      (node (ref "U$1") (pin "P$84") (pinfunction "VSS_PAD_P$84") (pintype "bidirectional"))
      (node (ref "U$1") (pin "P$85") (pinfunction "VSS_PAD_P$85") (pintype "bidirectional"))
      (node (ref "U$1") (pin "P$86") (pinfunction "VSS_PAD_P$86") (pintype "bidirectional"))
      (node (ref "U$1") (pin "P$87") (pinfunction "VSS_PAD_P$87") (pintype "bidirectional"))
      (node (ref "U$1") (pin "P$88") (pinfunction "VSS_PAD_P$88") (pintype "bidirectional"))
      (node (ref "U$1") (pin "P$89") (pinfunction "VSS_PAD_P$89") (pintype "bidirectional"))
      (node (ref "U$1") (pin "P$90") (pinfunction "VSS_PAD_P$90") (pintype "bidirectional"))
      (node (ref "U$1") (pin "P$B7") (pinfunction "VSS_P$B7") (pintype "power_in"))
      (node (ref "U$1") (pin "P$F23") (pinfunction "VSS_PA_P$F23") (pintype "bidirectional"))
      (node (ref "U$10") (pin "2") (pinfunction "2_2") (pintype "passive"))
      (node (ref "U$13") (pin "2") (pinfunction "2_2") (pintype "passive"))
      (node (ref "U$14") (pin "2") (pinfunction "2_2") (pintype "passive"))
      (node (ref "U$15") (pin "1") (pinfunction "1_1") (pintype "passive"))
      (node (ref "U$16") (pin "1") (pinfunction "1_1") (pintype "passive"))
      (node (ref "U$17") (pin "1") (pinfunction "1_1") (pintype "passive"))
      (node (ref "U$18") (pin "1") (pinfunction "1_1") (pintype "passive"))
      (node (ref "U$19") (pin "1") (pinfunction "1_1") (pintype "passive"))
      (node (ref "U$2") (pin "1") (pinfunction "1_1") (pintype "passive"))
      (node (ref "U$20") (pin "1") (pinfunction "1_1") (pintype "passive"))
      (node (ref "U$21") (pin "1") (pinfunction "1_1") (pintype "passive"))
      (node (ref "U$22") (pin "1") (pinfunction "1_1") (pintype "passive"))
      (node (ref "U$23") (pin "1") (pinfunction "1_1") (pintype "passive"))
      (node (ref "U$24") (pin "1") (pinfunction "1_1") (pintype "passive"))
      (node (ref "U$25") (pin "2") (pinfunction "2_2") (pintype "passive"))
      (node (ref "U$26") (pin "2") (pinfunction "2_2") (pintype "passive"))
      (node (ref "U$27") (pin "2") (pinfunction "2_2") (pintype "passive"))
      (node (ref "U$28") (pin "2") (pinfunction "2_2") (pintype "passive"))
      (node (ref "U$29") (pin "2") (pinfunction "2_2") (pintype "passive"))
      (node (ref "U$3") (pin "1") (pinfunction "1_1") (pintype "passive"))
      (node (ref "U$30") (pin "2") (pinfunction "2_2") (pintype "passive"))
      (node (ref "U$31") (pin "2") (pinfunction "2_2") (pintype "passive"))
      (node (ref "U$34") (pin "2") (pinfunction "2_2") (pintype "passive"))
      (node (ref "U$35") (pin "2") (pinfunction "2_2") (pintype "passive"))
      (node (ref "U$36") (pin "2") (pinfunction "2_2") (pintype "passive"))
      (node (ref "U$37") (pin "2") (pinfunction "2_2") (pintype "passive"))
      (node (ref "U$38") (pin "2") (pinfunction "2_2") (pintype "passive"))
      (node (ref "U$39") (pin "2") (pinfunction "2_2") (pintype "passive"))
      (node (ref "U$40") (pin "2") (pinfunction "2_2") (pintype "passive"))
      (node (ref "U$41") (pin "2") (pinfunction "2_2") (pintype "passive"))
      (node (ref "U$42") (pin "2") (pinfunction "2_2") (pintype "passive"))
      (node (ref "U$43") (pin "2") (pinfunction "2_2") (pintype "passive"))
      (node (ref "U$43") (pin "4") (pinfunction "4_4") (pintype "passive"))
      (node (ref "U$44") (pin "2") (pinfunction "2_2") (pintype "passive"))
      (node (ref "U$45") (pin "2") (pinfunction "2_2") (pintype "passive"))
      (node (ref "U$47") (pin "2") (pinfunction "2_2") (pintype "passive"))
      (node (ref "U$48") (pin "2") (pinfunction "2_2") (pintype "passive"))
      (node (ref "U$49") (pin "2") (pinfunction "2_2") (pintype "passive"))
      (node (ref "U$5") (pin "1") (pinfunction "1_1") (pintype "passive"))
      (node (ref "U$50") (pin "1") (pinfunction "1_1") (pintype "passive"))
      (node (ref "U$51") (pin "1") (pinfunction "1_1") (pintype "passive"))
      (node (ref "U$52") (pin "2") (pinfunction "2_2") (pintype "passive"))
      (node (ref "U$53") (pin "2") (pinfunction "2_2") (pintype "passive"))
      (node (ref "U$54") (pin "2") (pinfunction "2_2") (pintype "passive"))
      (node (ref "U$6") (pin "1") (pinfunction "1_1") (pintype "passive"))
      (node (ref "U$7") (pin "2") (pinfunction "2_2") (pintype "passive"))
      (node (ref "U$8") (pin "2") (pinfunction "2_2") (pintype "passive"))
      (node (ref "U$9") (pin "2") (pinfunction "2_2") (pintype "passive"))
      (node (ref "U1") (pin "1") (pinfunction "CTG_1") (pintype "power_in"))
      (node (ref "U1") (pin "4") (pinfunction "GND_4") (pintype "power_in"))
      (node (ref "U1") (pin "6") (pinfunction "QSTRT_6") (pintype "input"))
      (node (ref "U1") (pin "9") (pinfunction "EP_9") (pintype "power_in"))
    )
    (net (code "22") (name "HAPTIC_EN{slash}1.4C") (class "Default")
      (node (ref "IC4") (pin "A1") (pinfunction "EN_A1") (pintype "bidirectional"))
    )
    (net (code "23") (name "HAPTIC_EN{slash}2.6A") (class "Default")
      (node (ref "U$1") (pin "P$U1") (pinfunction "P0.12_P$U1") (pintype "bidirectional"))
    )
    (net (code "24") (name "IMU_INT1") (class "Default")
      (node (ref "IC3") (pin "5") (pinfunction "INT1_5") (pintype "bidirectional"))
      (node (ref "U$1") (pin "P$N1") (pinfunction "P0.08_P$N1") (pintype "bidirectional"))
    )
    (net (code "25") (name "IMU_INT2") (class "Default")
      (node (ref "IC3") (pin "6") (pinfunction "INT2_6") (pintype "bidirectional"))
      (node (ref "U$1") (pin "P$P2") (pinfunction "P1.08_P$P2") (pintype "bidirectional"))
    )
    (net (code "26") (name "LX1") (class "Default")
      (node (ref "IC2") (pin "B2") (pinfunction "SW1_1_B2") (pintype "bidirectional"))
      (node (ref "IC2") (pin "B3") (pinfunction "SW1_2_B3") (pintype "bidirectional"))
      (node (ref "L1") (pin "1") (pinfunction "1_1") (pintype "bidirectional"))
    )
    (net (code "27") (name "LX2") (class "Default")
      (node (ref "IC2") (pin "D2") (pinfunction "SW2_1_D2") (pintype "bidirectional"))
      (node (ref "IC2") (pin "D3") (pinfunction "SW2_2_D3") (pintype "bidirectional"))
      (node (ref "L1") (pin "2") (pinfunction "2_2") (pintype "bidirectional"))
    )
    (net (code "28") (name "MOSI{slash}1.5B") (class "Default")
      (node (ref "J1") (pin "14") (pinfunction "14_14") (pintype "bidirectional"))
    )
    (net (code "29") (name "MOSI{slash}2.2D") (class "Default")
      (node (ref "U$1") (pin "P$B13") (pinfunction "P0.03/AIN1_P$B13") (pintype "bidirectional"))
    )
    (net (code "30") (name "Net-(ANT1-FEED)") (class "Default")
      (node (ref "ANT1") (pin "1") (pinfunction "FEED_1") (pintype "input"))
      (node (ref "U$40") (pin "1") (pinfunction "1_1") (pintype "passive"))
      (node (ref "U$41") (pin "1") (pinfunction "1_1") (pintype "passive"))
      (node (ref "U$46") (pin "2") (pinfunction "2_2") (pintype "passive"))
    )
    (net (code "31") (name "Net-(D1-A)") (class "Default")
      (node (ref "D1") (pin "2") (pinfunction "A_2") (pintype "bidirectional"))
      (node (ref "D2") (pin "1") (pinfunction "K_1") (pintype "bidirectional"))
      (node (ref "U$12") (pin "1") (pinfunction "1_1") (pintype "passive"))
    )
    (net (code "32") (name "Net-(D3-A)") (class "Default")
      (node (ref "D3") (pin "2") (pinfunction "A_2") (pintype "bidirectional"))
      (node (ref "Q1") (pin "3") (pinfunction "D_3") (pintype "bidirectional"))
      (node (ref "U$11") (pin "2") (pinfunction "2_2") (pintype "passive"))
      (node (ref "U$12") (pin "2") (pinfunction "2_2") (pintype "passive"))
    )
    (net (code "33") (name "Net-(IC1-TS{slash}MR)") (class "Default")
      (node (ref "IC1") (pin "D1") (pinfunction "TS/MR_D1") (pintype "bidirectional"))
      (node (ref "R1") (pin "2") (pinfunction "2_2") (pintype "passive"))
    )
    (net (code "34") (name "Net-(IC2-SCL)") (class "Default")
      (node (ref "IC2") (pin "D1") (pinfunction "SCL_D1") (pintype "bidirectional"))
      (node (ref "R3") (pin "1") (pinfunction "1_1") (pintype "passive"))
    )
    (net (code "35") (name "Net-(IC2-SDA)") (class "Default")
      (node (ref "IC2") (pin "E1") (pinfunction "SDA_E1") (pintype "bidirectional"))
      (node (ref "R2") (pin "1") (pinfunction "1_1") (pintype "passive"))
    )
    (net (code "36") (name "Net-(IC3-SDO)") (class "Default")
      (node (ref "IC3") (pin "1") (pinfunction "SDO_1") (pintype "bidirectional"))
      (node (ref "R6") (pin "1") (pinfunction "1_1") (pintype "passive"))
    )
    (net (code "37") (name "Net-(IC4-REG)") (class "Default")
      (node (ref "IC4") (pin "A2") (pinfunction "REG_A2") (pintype "bidirectional"))
      (node (ref "U$26") (pin "1") (pinfunction "1_1") (pintype "passive"))
    )
    (net (code "38") (name "Net-(J1-Pad4)") (class "Default")
      (node (ref "J1") (pin "4") (pinfunction "4_4") (pintype "bidirectional"))
      (node (ref "U$22") (pin "2") (pinfunction "2_2") (pintype "passive"))
    )
    (net (code "39") (name "Net-(J1-Pad5)") (class "Default")
      (node (ref "J1") (pin "5") (pinfunction "5_5") (pintype "bidirectional"))
      (node (ref "U$23") (pin "2") (pinfunction "2_2") (pintype "passive"))
    )
    (net (code "40") (name "Net-(J1-Pad18)") (class "Default")
      (node (ref "J1") (pin "18") (pinfunction "18_18") (pintype "bidirectional"))
      (node (ref "U$15") (pin "2") (pinfunction "2_2") (pintype "passive"))
    )
    (net (code "41") (name "Net-(J1-Pad19)") (class "Default")
      (node (ref "J1") (pin "19") (pinfunction "19_19") (pintype "bidirectional"))
      (node (ref "U$16") (pin "2") (pinfunction "2_2") (pintype "passive"))
    )
    (net (code "42") (name "Net-(J1-Pad20)") (class "Default")
      (node (ref "J1") (pin "20") (pinfunction "20_20") (pintype "bidirectional"))
      (node (ref "U$17") (pin "2") (pinfunction "2_2") (pintype "passive"))
    )
    (net (code "43") (name "Net-(J1-Pad22)") (class "Default")
      (node (ref "J1") (pin "22") (pinfunction "22_22") (pintype "bidirectional"))
      (node (ref "U$19") (pin "2") (pinfunction "2_2") (pintype "passive"))
    )
    (net (code "44") (name "Net-(J1-Pad24)") (class "Default")
      (node (ref "J1") (pin "24") (pinfunction "24_24") (pintype "bidirectional"))
      (node (ref "U$21") (pin "2") (pinfunction "2_2") (pintype "passive"))
    )
    (net (code "45") (name "Net-(J2-CC1)") (class "Default")
      (node (ref "J2") (pin "A5") (pinfunction "CC1_A5") (pintype "bidirectional"))
      (node (ref "R12") (pin "2") (pinfunction "2_2") (pintype "bidirectional"))
    )
    (net (code "46") (name "Net-(J2-CC2)") (class "Default")
      (node (ref "J2") (pin "B5") (pinfunction "CC2_B5") (pintype "bidirectional"))
      (node (ref "R11") (pin "1") (pinfunction "1_1") (pintype "bidirectional"))
    )
    (net (code "47") (name "Net-(R7-Pad1)") (class "Default")
      (node (ref "R7") (pin "1") (pinfunction "1_1") (pintype "passive"))
      (node (ref "R8") (pin "2") (pinfunction "2_2") (pintype "passive"))
      (node (ref "SJ1") (pin "2") (pinfunction "2_2") (pintype "passive"))
    )
    (net (code "48") (name "Net-(U$1-ANT)") (class "Default")
      (node (ref "U$1") (pin "P$H23") (pinfunction "ANT_P$H23") (pintype "bidirectional"))
      (node (ref "U$42") (pin "1") (pinfunction "1_1") (pintype "passive"))
      (node (ref "U$46") (pin "1") (pinfunction "1_1") (pintype "passive"))
    )
    (net (code "49") (name "Net-(U$1-DCC)") (class "Default")
      (node (ref "U$1") (pin "P$B3") (pinfunction "DCC_P$B3") (pintype "output"))
      (node (ref "U$32") (pin "1") (pinfunction "1_1") (pintype "passive"))
    )
    (net (code "50") (name "Net-(U$1-DEC1)") (class "Default")
      (node (ref "U$1") (pin "P$C1") (pinfunction "DEC1_P$C1") (pintype "power_in"))
      (node (ref "U$5") (pin "2") (pinfunction "2_2") (pintype "passive"))
    )
    (net (code "51") (name "Net-(U$1-DEC2)") (class "Default")
      (node (ref "U$1") (pin "P$A18") (pinfunction "DEC2_P$A18") (pintype "bidirectional"))
      (node (ref "U$36") (pin "1") (pinfunction "1_1") (pintype "passive"))
    )
    (net (code "52") (name "Net-(U$1-DEC3)") (class "Default")
      (node (ref "U$1") (pin "P$D23") (pinfunction "DEC3_P$D23") (pintype "bidirectional"))
      (node (ref "U$38") (pin "1") (pinfunction "1_1") (pintype "passive"))
    )
    (net (code "53") (name "Net-(U$1-DEC3V3)") (class "Default")
      (node (ref "U$1") (pin "P$AC5") (pinfunction "DEC3V3_P$AC5") (pintype "bidirectional"))
      (node (ref "U$8") (pin "1") (pinfunction "1_1") (pintype "passive"))
    )
    (net (code "54") (name "Net-(U$1-DEC4)") (class "Default")
      (node (ref "U$1") (pin "P$B5") (pinfunction "DEC4_P$B5") (pintype "power_in"))
      (node (ref "U$1") (pin "P$E24") (pinfunction "DEC6_P$E24") (pintype "bidirectional"))
      (node (ref "U$33") (pin "2") (pinfunction "2_2") (pintype "passive"))
      (node (ref "U$34") (pin "1") (pinfunction "1_1") (pintype "passive"))
      (node (ref "U$35") (pin "1") (pinfunction "1_1") (pintype "passive"))
      (node (ref "U$39") (pin "1") (pinfunction "1_1") (pintype "passive"))
    )
    (net (code "55") (name "Net-(U$1-DEC5)") (class "Default")
      (node (ref "C9") (pin "1") (pinfunction "1_1") (pintype "passive"))
      (node (ref "U$1") (pin "P$N24") (pinfunction "DEC5_P$N24") (pintype "bidirectional"))
    )
    (net (code "56") (name "Net-(U$1-P0.00{slash}XL1)") (class "Default")
      (node (ref "U$1") (pin "P$D2") (pinfunction "P0.00/XL1_P$D2") (pintype "bidirectional"))
      (node (ref "U$3") (pin "2") (pinfunction "2_2") (pintype "passive"))
      (node (ref "U$4") (pin "2") (pinfunction "2_2") (pintype "passive"))
    )
    (net (code "57") (name "Net-(U$1-P0.01{slash}XL2)") (class "Default")
      (node (ref "U$1") (pin "P$F2") (pinfunction "P0.01/XL2_P$F2") (pintype "bidirectional"))
      (node (ref "U$2") (pin "2") (pinfunction "2_2") (pintype "passive"))
      (node (ref "U$4") (pin "1") (pinfunction "1_1") (pintype "passive"))
    )
    (net (code "58") (name "Net-(U$1-XC1)") (class "Default")
      (node (ref "U$1") (pin "P$B24") (pinfunction "XC1_P$B24") (pintype "input"))
      (node (ref "U$43") (pin "1") (pinfunction "1_1") (pintype "passive"))
      (node (ref "U$44") (pin "1") (pinfunction "1_1") (pintype "passive"))
    )
    (net (code "59") (name "Net-(U$1-XC2)") (class "Default")
      (node (ref "U$1") (pin "P$A23") (pinfunction "XC2_P$A23") (pintype "output"))
      (node (ref "U$43") (pin "3") (pinfunction "3_3") (pintype "passive"))
      (node (ref "U$45") (pin "1") (pinfunction "1_1") (pintype "passive"))
    )
    (net (code "60") (name "Net-(U$32-Pad2)") (class "Default")
      (node (ref "U$32") (pin "2") (pinfunction "2_2") (pintype "passive"))
      (node (ref "U$33") (pin "1") (pinfunction "1_1") (pintype "passive"))
    )
    (net (code "61") (name "OUT+") (class "Default")
      (node (ref "IC4") (pin "A3") (pinfunction "OUT+_A3") (pintype "bidirectional"))
    )
    (net (code "62") (name "OUT-") (class "Default")
      (node (ref "IC4") (pin "C3") (pinfunction "OUT-_C3") (pintype "bidirectional"))
    )
    (net (code "63") (name "P0.04") (class "Default")
      (node (ref "U$1") (pin "P$J1") (pinfunction "P0.04/AIN2_P$J1") (pintype "bidirectional"))
    )
    (net (code "64") (name "P0.09") (class "Default")
      (node (ref "U$1") (pin "P$L24") (pinfunction "P0.09/NFC1_P$L24") (pintype "bidirectional"))
    )
    (net (code "65") (name "P0.13{slash}1.5D") (class "Default")
      (node (ref "R13") (pin "1") (pinfunction "1_1") (pintype "bidirectional"))
      (node (ref "SW1") (pin "2") (pinfunction "2_2") (pintype "passive"))
      (node (ref "U$29") (pin "1") (pinfunction "1_1") (pintype "passive"))
    )
    (net (code "66") (name "P0.13{slash}2.6C") (class "Default")
      (node (ref "U$1") (pin "P$AD8") (pinfunction "P0.13_P$AD8") (pintype "bidirectional"))
    )
    (net (code "67") (name "P0.13{slash}2.7C") (class "Default")
      (node (ref "U$1") (pin "P$AC9") (pinfunction "P0.14_P$AC9") (pintype "bidirectional"))
    )
    (net (code "68") (name "P0.14{slash}1.5D") (class "Default")
      (node (ref "R14") (pin "1") (pinfunction "1_1") (pintype "bidirectional"))
      (node (ref "SW2") (pin "2") (pinfunction "2_2") (pintype "passive"))
      (node (ref "U$30") (pin "1") (pinfunction "1_1") (pintype "passive"))
    )
    (net (code "69") (name "P0.19") (class "Default")
      (node (ref "U$1") (pin "P$AC15") (pinfunction "P0.19_P$AC15") (pintype "bidirectional"))
    )
    (net (code "70") (name "P0.20") (class "Default")
      (node (ref "U$1") (pin "P$AD16") (pinfunction "P0.20_P$AD16") (pintype "bidirectional"))
    )
    (net (code "71") (name "P0.21") (class "Default")
      (node (ref "U$1") (pin "P$AC17") (pinfunction "P0.21_P$AC17") (pintype "bidirectional"))
    )
    (net (code "72") (name "P0.22") (class "Default")
      (node (ref "U$1") (pin "P$AD18") (pinfunction "P0.22_P$AD18") (pintype "bidirectional"))
    )
    (net (code "73") (name "P0.23") (class "Default")
      (node (ref "U$1") (pin "P$AC19") (pinfunction "P0.23_P$AC19") (pintype "bidirectional"))
    )
    (net (code "74") (name "P0.24") (class "Default")
      (node (ref "U$1") (pin "P$AD20") (pinfunction "P0.24_P$AD20") (pintype "bidirectional"))
    )
    (net (code "75") (name "P0.25") (class "Default")
      (node (ref "U$1") (pin "P$AC21") (pinfunction "P0.25_P$AC21") (pintype "bidirectional"))
    )
    (net (code "76") (name "P0.26") (class "Default")
      (node (ref "U$1") (pin "P$G1") (pinfunction "P0.26_P$G1") (pintype "bidirectional"))
    )
    (net (code "77") (name "P0.27") (class "Default")
      (node (ref "U$1") (pin "P$H2") (pinfunction "P0.27_P$H2") (pintype "bidirectional"))
    )
    (net (code "78") (name "P0.28") (class "Default")
      (node (ref "U$1") (pin "P$B11") (pinfunction "P0.28/AIN4_P$B11") (pintype "bidirectional"))
    )
    (net (code "79") (name "P0.29") (class "Default")
      (node (ref "U$1") (pin "P$A10") (pinfunction "P0.29/AIN5_P$A10") (pintype "bidirectional"))
    )
    (net (code "80") (name "P0.30") (class "Default")
      (node (ref "U$1") (pin "P$B9") (pinfunction "P0.30/AIN6_P$B9") (pintype "bidirectional"))
    )
    (net (code "81") (name "P0.31") (class "Default")
      (node (ref "U$1") (pin "P$A8") (pinfunction "P0.31/AIN7_P$A8") (pintype "bidirectional"))
    )
    (net (code "82") (name "P1.01{slash}1.6C") (class "Default")
      (node (ref "Q2") (pin "1") (pinfunction "G_1") (pintype "bidirectional"))
      (node (ref "R10") (pin "1") (pinfunction "1_1") (pintype "bidirectional"))
    )
    (net (code "83") (name "P1.01{slash}2.4B") (class "Default")
      (node (ref "U$1") (pin "P$Y23") (pinfunction "P1.01_P$Y23") (pintype "bidirectional"))
    )
    (net (code "84") (name "P1.02{slash}1.6C") (class "Default")
      (node (ref "R15") (pin "1") (pinfunction "1_1") (pintype "bidirectional"))
      (node (ref "SW3") (pin "2") (pinfunction "2_2") (pintype "passive"))
      (node (ref "U$31") (pin "1") (pinfunction "1_1") (pintype "passive"))
    )
    (net (code "85") (name "P1.02{slash}2.8C") (class "Default")
      (node (ref "U$1") (pin "P$W24") (pinfunction "P1.02_P$W24") (pintype "bidirectional"))
    )
    (net (code "86") (name "P1.03") (class "Default")
      (node (ref "U$1") (pin "P$V23") (pinfunction "P1.03_P$V23") (pintype "bidirectional"))
    )
    (net (code "87") (name "P1.04") (class "Default")
      (node (ref "U$1") (pin "P$U24") (pinfunction "P1.04_P$U24") (pintype "bidirectional"))
    )
    (net (code "88") (name "P1.05") (class "Default")
      (node (ref "U$1") (pin "P$T23") (pinfunction "P1.05_P$T23") (pintype "bidirectional"))
    )
    (net (code "89") (name "P1.06") (class "Default")
      (node (ref "U$1") (pin "P$R24") (pinfunction "P1.06_P$R24") (pintype "bidirectional"))
    )
    (net (code "90") (name "P1.07") (class "Default")
      (node (ref "U$1") (pin "P$P23") (pinfunction "P1.07_P$P23") (pintype "bidirectional"))
    )
    (net (code "91") (name "P1.09") (class "Default")
      (node (ref "U$1") (pin "P$R1") (pinfunction "P1.09_P$R1") (pintype "bidirectional"))
    )
    (net (code "92") (name "P1.10") (class "Default")
      (node (ref "U$1") (pin "P$A20") (pinfunction "P1.10_P$A20") (pintype "bidirectional"))
    )
    (net (code "93") (name "P1.11") (class "Default")
      (node (ref "U$1") (pin "P$B19") (pinfunction "P1.11_P$B19") (pintype "bidirectional"))
    )
    (net (code "94") (name "P1.12") (class "Default")
      (node (ref "U$1") (pin "P$B17") (pinfunction "P1.12_P$B17") (pintype "bidirectional"))
    )
    (net (code "95") (name "P1.13") (class "Default")
      (node (ref "U$1") (pin "P$A16") (pinfunction "P1.13_P$A16") (pintype "bidirectional"))
    )
    (net (code "96") (name "P1.14") (class "Default")
      (node (ref "U$1") (pin "P$B15") (pinfunction "P1.14_P$B15") (pintype "bidirectional"))
    )
    (net (code "97") (name "P1.15") (class "Default")
      (node (ref "U$1") (pin "P$A14") (pinfunction "P1.15_P$A14") (pintype "bidirectional"))
    )
    (net (code "98") (name "PMIC_INT") (class "Default")
      (node (ref "IC1") (pin "A1") (pinfunction "~{INT}_A1") (pintype "bidirectional"))
      (node (ref "U$1") (pin "P$T2") (pinfunction "P0.11_P$T2") (pintype "bidirectional"))
    )
    (net (code "99") (name "PREVGH") (class "Default")
      (node (ref "D3") (pin "1") (pinfunction "K_1") (pintype "bidirectional"))
      (node (ref "J1") (pin "21") (pinfunction "21_21") (pintype "bidirectional"))
      (node (ref "U$18") (pin "2") (pinfunction "2_2") (pintype "passive"))
    )
    (net (code "100") (name "PREVGL") (class "Default")
      (node (ref "D2") (pin "2") (pinfunction "A_2") (pintype "bidirectional"))
      (node (ref "J1") (pin "23") (pinfunction "23_23") (pintype "bidirectional"))
      (node (ref "U$20") (pin "2") (pinfunction "2_2") (pintype "passive"))
    )
    (net (code "101") (name "RESE") (class "Default")
      (node (ref "J1") (pin "3") (pinfunction "3_3") (pintype "bidirectional"))
      (node (ref "Q1") (pin "2") (pinfunction "S_2") (pintype "bidirectional"))
      (node (ref "R7") (pin "2") (pinfunction "2_2") (pintype "passive"))
    )
    (net (code "102") (name "RESET") (class "Default")
      (node (ref "J3") (pin "6") (pinfunction "6_6") (pintype "bidirectional"))
      (node (ref "TP8") (pin "TP") (pinfunction "TP_TP") (pintype "input"))
      (node (ref "U$1") (pin "P$AC13") (pinfunction "P0.18/RESET_P$AC13") (pintype "bidirectional"))
    )
    (net (code "103") (name "SCK{slash}1.5B") (class "Default")
      (node (ref "J1") (pin "13") (pinfunction "13_13") (pintype "bidirectional"))
    )
    (net (code "104") (name "SCK{slash}2.2D") (class "Default")
      (node (ref "U$1") (pin "P$A12") (pinfunction "P0.02/AIN0_P$A12") (pintype "bidirectional"))
    )
    (net (code "105") (name "SCL{slash}1.4C") (class "Default")
      (node (ref "IC4") (pin "C1") (pinfunction "SCL_C1") (pintype "bidirectional"))
      (node (ref "U1") (pin "7") (pinfunction "SCL_7") (pintype "input"))
    )
    (net (code "106") (name "SCL{slash}2.4C") (class "Default")
      (node (ref "IC1") (pin "B1") (pinfunction "SCL_B1") (pintype "bidirectional"))
      (node (ref "IC3") (pin "12") (pinfunction "SCX_12") (pintype "bidirectional"))
      (node (ref "R3") (pin "2") (pinfunction "2_2") (pintype "passive"))
      (node (ref "R4") (pin "2") (pinfunction "2_2") (pintype "passive"))
      (node (ref "TP4") (pin "TP") (pinfunction "TP_TP") (pintype "input"))
      (node (ref "U$1") (pin "P$M2") (pinfunction "P0.07_P$M2") (pintype "bidirectional"))
    )
    (net (code "107") (name "SDA{slash}1.4C") (class "Default")
      (node (ref "IC4") (pin "B2") (pinfunction "SDA_B2") (pintype "bidirectional"))
      (node (ref "U1") (pin "8") (pinfunction "SDA_8") (pintype "bidirectional"))
    )
    (net (code "108") (name "SDA{slash}2.4C") (class "Default")
      (node (ref "IC1") (pin "C1") (pinfunction "SDA_C1") (pintype "bidirectional"))
      (node (ref "IC3") (pin "2") (pinfunction "SDX_2") (pintype "bidirectional"))
      (node (ref "R2") (pin "2") (pinfunction "2_2") (pintype "passive"))
      (node (ref "R5") (pin "2") (pinfunction "2_2") (pintype "passive"))
      (node (ref "TP3") (pin "TP") (pinfunction "TP_TP") (pintype "input"))
      (node (ref "U$1") (pin "P$L1") (pinfunction "P0.06_P$L1") (pintype "bidirectional"))
    )
    (net (code "109") (name "SWDCLK") (class "Default")
      (node (ref "J3") (pin "4") (pinfunction "4_4") (pintype "bidirectional"))
      (node (ref "TP7") (pin "TP") (pinfunction "TP_TP") (pintype "input"))
      (node (ref "U$1") (pin "P$AA24") (pinfunction "SWDCLK_P$AA24") (pintype "input"))
    )
    (net (code "110") (name "SWDIO") (class "Default")
      (node (ref "J3") (pin "2") (pinfunction "2_2") (pintype "bidirectional"))
      (node (ref "TP6") (pin "TP") (pinfunction "TP_TP") (pintype "input"))
      (node (ref "U$1") (pin "P$AC24") (pinfunction "SWDIO_P$AC24") (pintype "bidirectional"))
    )
    (net (code "111") (name "SWO") (class "Default")
      (node (ref "TP5") (pin "TP") (pinfunction "TP_TP") (pintype "input"))
      (node (ref "U$1") (pin "P$AD22") (pinfunction "P1.00_P$AD22") (pintype "bidirectional"))
    )
    (net (code "112") (name "VBAT{slash}1.2A") (class "Default")
      (node (ref "TP2") (pin "TP") (pinfunction "TP_TP") (pintype "input"))
      (node (ref "U$14") (pin "1") (pinfunction "1_1") (pintype "passive"))
      (node (ref "U1") (pin "2") (pinfunction "CELL_2") (pintype "power_in"))
      (node (ref "U1") (pin "3") (pinfunction "VDD_3") (pintype "power_in"))
    )
    (net (code "113") (name "VBAT{slash}2.5C") (class "Default")
      (node (ref "IC1") (pin "C2") (pinfunction "BAT_C2") (pintype "bidirectional"))
      (node (ref "U$49") (pin "1") (pinfunction "1_1") (pintype "passive"))
    )
    (net (code "114") (name "VBUS{slash}1.5D") (class "Default")
      (node (ref "D4") (pin "5") (pinfunction "VBUS_5") (pintype "bidirectional"))
      (node (ref "J2") (pin "A4_B9") (pinfunction "VBUS_A4_B9") (pintype "power_in"))
      (node (ref "J2") (pin "A9_B4") (pinfunction "VBUS_A9_B4") (pintype "power_in"))
      (node (ref "U$27") (pin "1") (pinfunction "1_1") (pintype "passive"))
      (node (ref "U$28") (pin "1") (pinfunction "1_1") (pintype "passive"))
    )
    (net (code "115") (name "VBUS{slash}2.6D") (class "Default")
      (node (ref "IC1") (pin "A2") (pinfunction "IN_A2") (pintype "bidirectional"))
      (node (ref "U$1") (pin "P$AD2") (pinfunction "VBUS_P$AD2") (pintype "power_in"))
      (node (ref "U$47") (pin "1") (pinfunction "1_1") (pintype "passive"))
      (node (ref "U$9") (pin "1") (pinfunction "1_1") (pintype "passive"))
    )
    (net (code "116") (name "VREG") (class "Default")
      (node (ref "IC1") (pin "B2") (pinfunction "SYS_B2") (pintype "bidirectional"))
      (node (ref "IC2") (pin "A1") (pinfunction "EN_A1") (pintype "bidirectional"))
      (node (ref "IC2") (pin "A2") (pinfunction "VIN_1_A2") (pintype "bidirectional"))
      (node (ref "IC2") (pin "A3") (pinfunction "VIN_2_A3") (pintype "bidirectional"))
      (node (ref "U$48") (pin "1") (pinfunction "1_1") (pintype "passive"))
      (node (ref "U$50") (pin "2") (pinfunction "2_2") (pintype "passive"))
      (node (ref "U$51") (pin "2") (pinfunction "2_2") (pintype "passive"))
    )
    (net (code "117") (name "unconnected-(ANT1-NC-Pad2)") (class "Default")
      (node (ref "ANT1") (pin "2") (pinfunction "NC_2") (pintype "no_connect"))
    )
    (net (code "118") (name "unconnected-(IC3-ASCL-Pad11)") (class "Default")
      (node (ref "IC3") (pin "11") (pinfunction "ASCL_11") (pintype "bidirectional"))
    )
    (net (code "119") (name "unconnected-(IC3-ASDA-Pad4)") (class "Default")
      (node (ref "IC3") (pin "4") (pinfunction "ASDA_4") (pintype "bidirectional"))
    )
    (net (code "120") (name "unconnected-(J1-Pad1)") (class "Default")
      (node (ref "J1") (pin "1") (pinfunction "1_1") (pintype "bidirectional"))
    )
    (net (code "121") (name "unconnected-(J1-Pad6)") (class "Default")
      (node (ref "J1") (pin "6") (pinfunction "6_6") (pintype "bidirectional"))
    )
    (net (code "122") (name "unconnected-(J1-Pad7)") (class "Default")
      (node (ref "J1") (pin "7") (pinfunction "7_7") (pintype "bidirectional"))
    )
    (net (code "123") (name "unconnected-(J2-SBU1-PadA8)") (class "Default")
      (node (ref "J2") (pin "A8") (pinfunction "SBU1_A8") (pintype "bidirectional"))
    )
    (net (code "124") (name "unconnected-(J2-SBU2-PadB8)") (class "Default")
      (node (ref "J2") (pin "B8") (pinfunction "SBU2_B8") (pintype "bidirectional"))
    )
    (net (code "125") (name "unconnected-(U$1-DCCH-PadP$AB2)") (class "Default")
      (node (ref "U$1") (pin "P$AB2") (pinfunction "DCCH_P$AB2") (pintype "bidirectional"))
    )
  )
)
